# SCH_Line_Following_Robot_Interrupt_2023-.net
KiCad netlist of a schematic drawn in EasyEDA
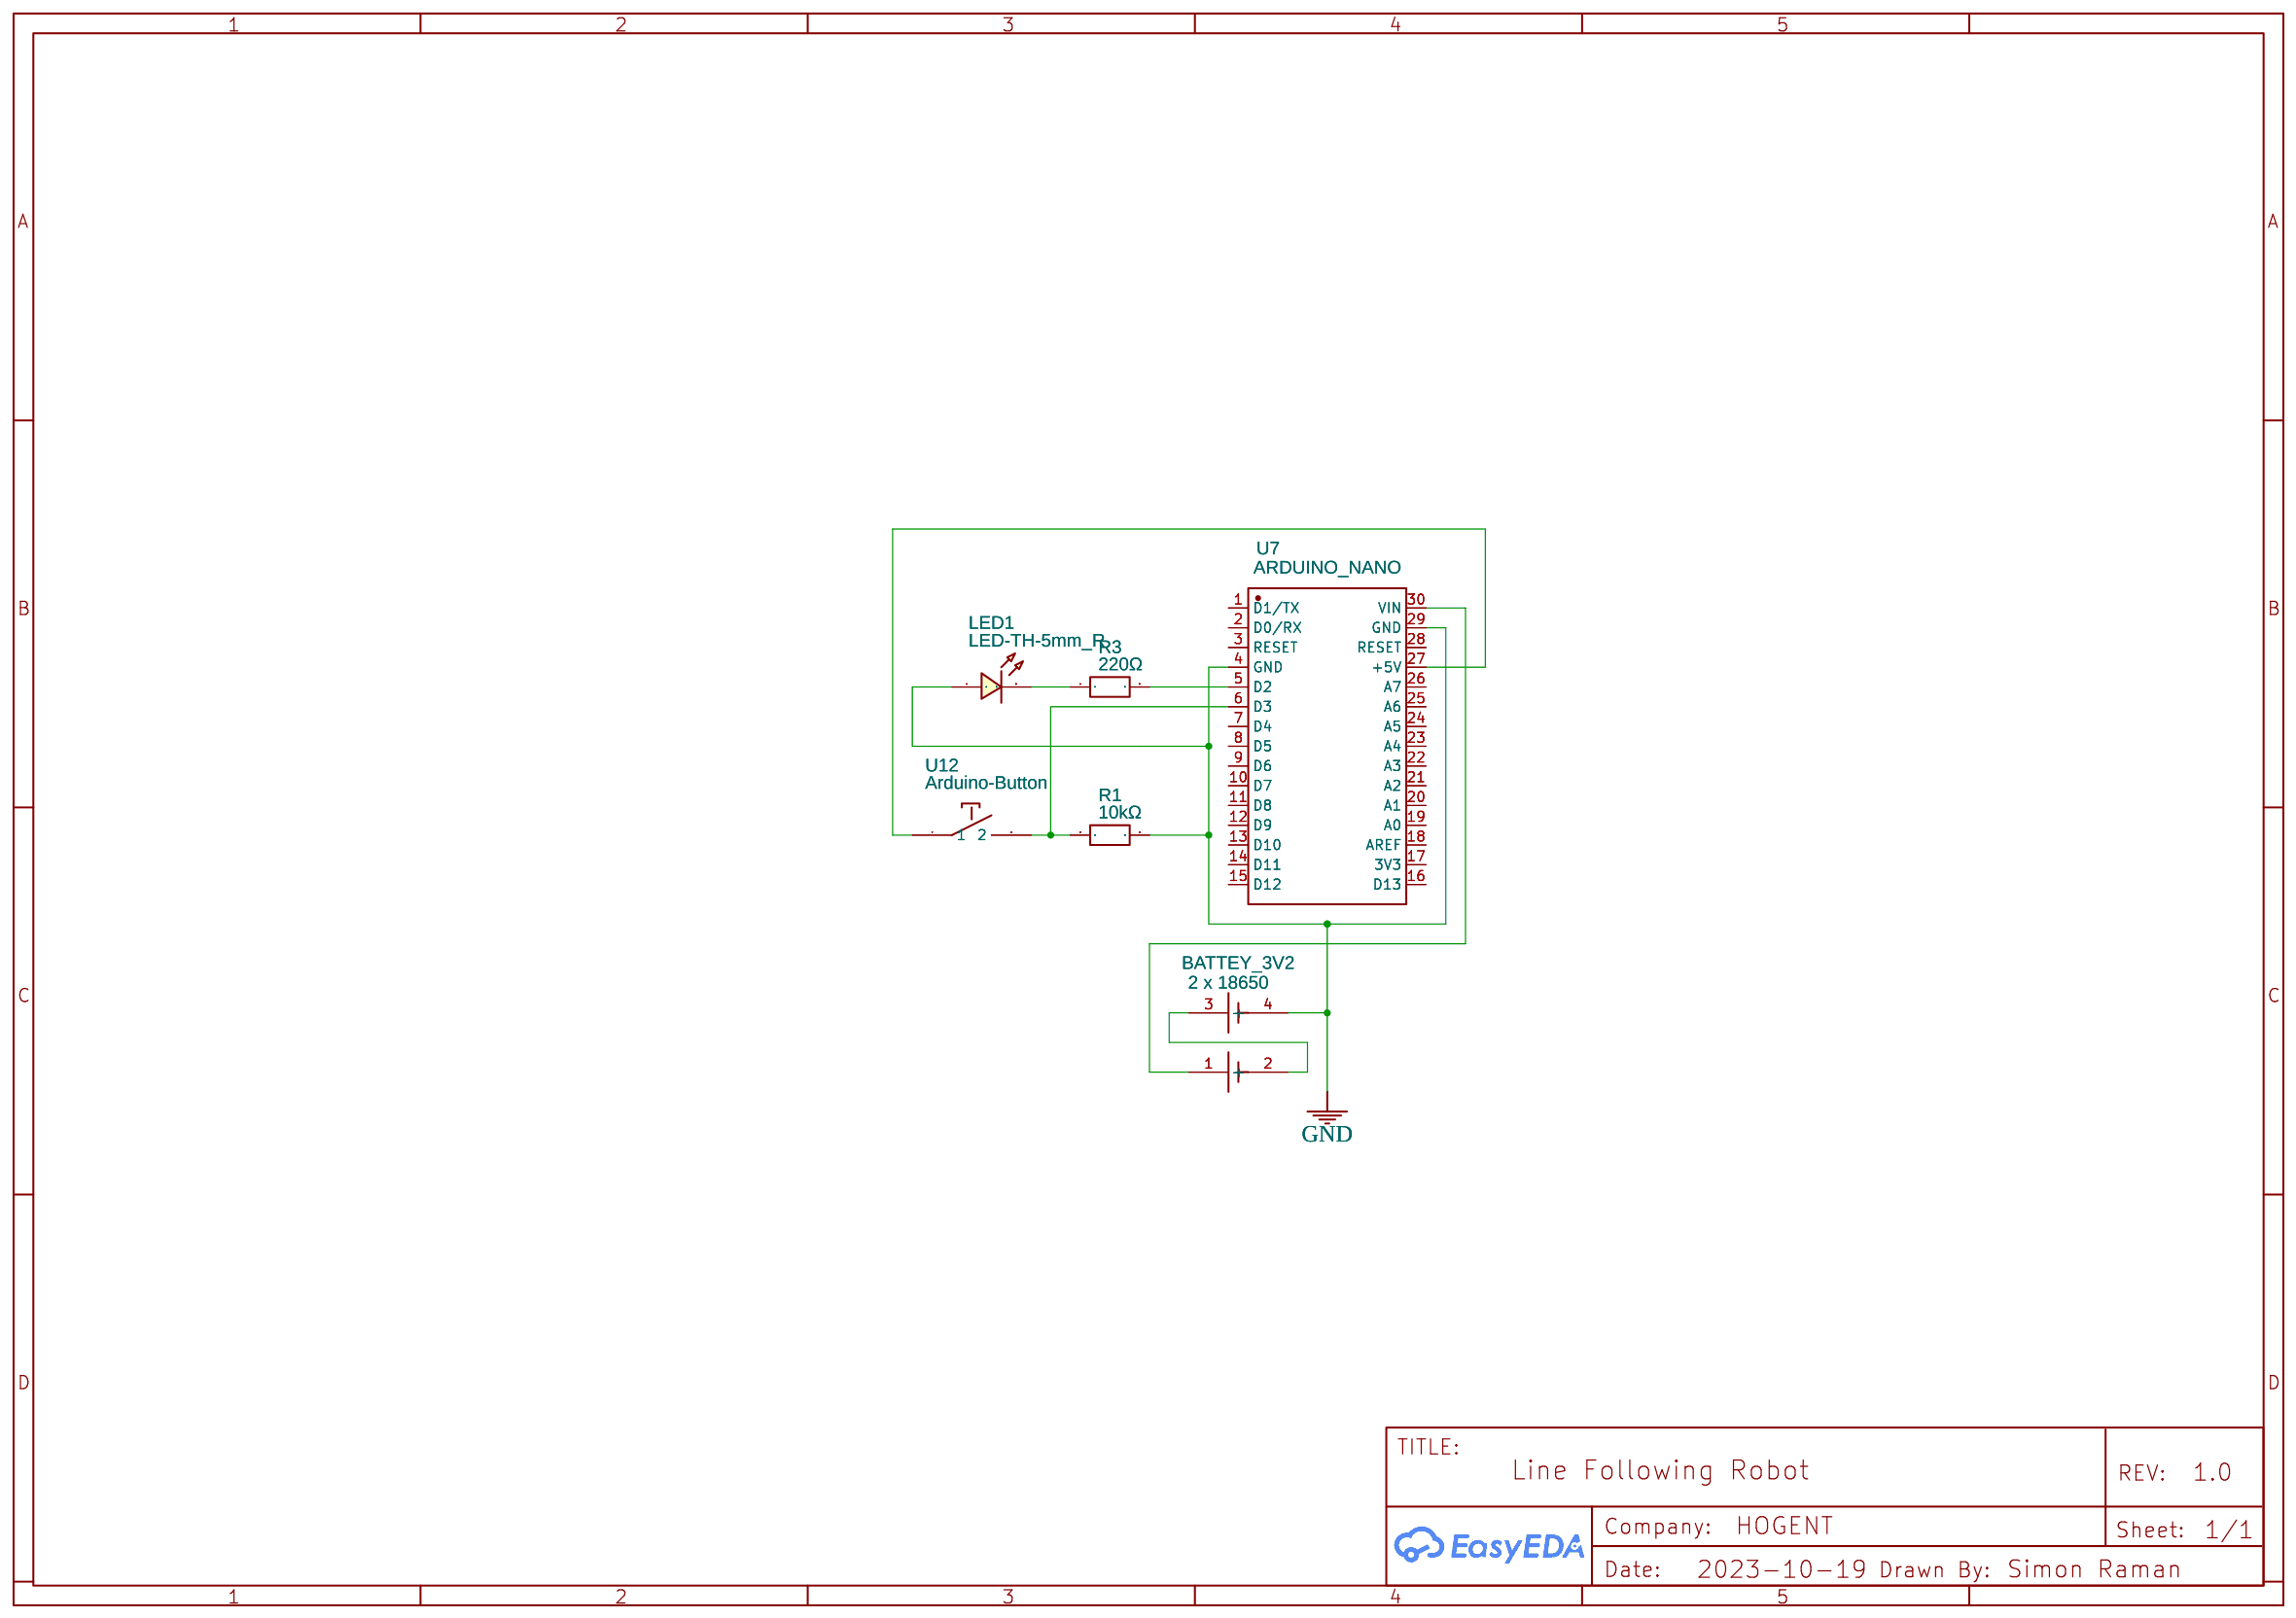
[diagram p0: schematic sheet]

(export (version "E")
  (design (tool "Eeschema 10.0.6"))
  (components
    (comp (ref "BATTEY_3V2")
      (value "2 x 18650")
      (fields (field (name "Manufacturer Part") "BAT_X2_18650") (field (name "Manufacturer") "Dex"))
      (libsource (lib "") (part "BAT_X2_18650"))
    )
    (comp (ref "LED1")
      (value "LED-TH-5mm_R")
      (fields
        (field (name "Manufacturer Part") "333-2SURD/S530-A3")
        (field (name "Manufacturer") "EVERLIGHT(台湾亿光)")
      )
      (libsource (lib "") (part "LED-TH-5mm_R"))
    )
    (comp (ref "R1")
      (value "10kΩ")
      (libsource (lib "") (part "AXIAL RESISTOR 220 OHM - TH_BD2.3-L6.0-P10.00-D0.4"))
    )
    (comp (ref "R3")
      (value "220Ω")
      (libsource (lib "") (part "AXIAL RESISTOR 220 OHM - TH_BD2.3-L6.0-P10.00-D0.4"))
    )
    (comp (ref "U7") (value "ARDUINO_NANO") (libsource (lib "") (part "ARDUINO_NANO")))
    (comp (ref "U12")
      (value "Arduino-Button")
      (fields (field (name "Manufacturer Part") "SW100664"))
      (libsource (lib "") (part "Arduino-Button"))
    )
  )
  (nets
    (net (code "1") (name "GND") (class "Default")
      (node (ref "BATTEY_3V2") (pin "4") (pinfunction "-_4") (pintype "unspecified"))
      (node (ref "LED1") (pin "1") (pinfunction "1_1") (pintype "unspecified"))
      (node (ref "R1") (pin "2") (pinfunction "2_2") (pintype "unspecified"))
      (node (ref "U7") (pin "29") (pinfunction "GND_29") (pintype "unspecified"))
      (node (ref "U7") (pin "4") (pinfunction "GND_4") (pintype "unspecified"))
    )
    (net (code "2") (name "Net-(BATTEY_3V2-+-Pad3)") (class "Default")
      (node (ref "BATTEY_3V2") (pin "2") (pinfunction "-_2") (pintype "unspecified"))
      (node (ref "BATTEY_3V2") (pin "3") (pinfunction "+_3") (pintype "unspecified"))
    )
    (net (code "3") (name "Net-(LED1-Pad2)") (class "Default")
      (node (ref "LED1") (pin "2") (pinfunction "2_2") (pintype "unspecified"))
      (node (ref "R3") (pin "1") (pinfunction "1_1") (pintype "unspecified"))
    )
    (net (code "4") (name "Net-(U7-+5V)") (class "Default")
      (node (ref "U12") (pin "1") (pinfunction "1_1") (pintype "unspecified"))
      (node (ref "U7") (pin "27") (pinfunction "+5V_27") (pintype "unspecified"))
    )
    (net (code "5") (name "Net-(U7-D2)") (class "Default")
      (node (ref "R3") (pin "2") (pinfunction "2_2") (pintype "unspecified"))
      (node (ref "U7") (pin "5") (pinfunction "D2_5") (pintype "unspecified"))
    )
    (net (code "6") (name "Net-(U7-D3)") (class "Default")
      (node (ref "R1") (pin "1") (pinfunction "1_1") (pintype "unspecified"))
      (node (ref "U12") (pin "2") (pinfunction "2_2") (pintype "unspecified"))
      (node (ref "U7") (pin "6") (pinfunction "D3_6") (pintype "unspecified"))
    )
    (net (code "7") (name "Net-(U7-VIN)") (class "Default")
      (node (ref "BATTEY_3V2") (pin "1") (pinfunction "+_1") (pintype "unspecified"))
      (node (ref "U7") (pin "30") (pinfunction "VIN_30") (pintype "unspecified"))
    )
    (net (code "8") (name "unconnected-(U7-3V3-Pad17)") (class "Default")
      (node (ref "U7") (pin "17") (pinfunction "3V3_17") (pintype "unspecified"))
    )
    (net (code "9") (name "unconnected-(U7-A0-Pad19)") (class "Default")
      (node (ref "U7") (pin "19") (pinfunction "A0_19") (pintype "unspecified"))
    )
    (net (code "10") (name "unconnected-(U7-A1-Pad20)") (class "Default")
      (node (ref "U7") (pin "20") (pinfunction "A1_20") (pintype "unspecified"))
    )
    (net (code "11") (name "unconnected-(U7-A2-Pad21)") (class "Default")
      (node (ref "U7") (pin "21") (pinfunction "A2_21") (pintype "unspecified"))
    )
    (net (code "12") (name "unconnected-(U7-A3-Pad22)") (class "Default")
      (node (ref "U7") (pin "22") (pinfunction "A3_22") (pintype "unspecified"))
    )
    (net (code "13") (name "unconnected-(U7-A4-Pad23)") (class "Default")
      (node (ref "U7") (pin "23") (pinfunction "A4_23") (pintype "unspecified"))
    )
    (net (code "14") (name "unconnected-(U7-A5-Pad24)") (class "Default")
      (node (ref "U7") (pin "24") (pinfunction "A5_24") (pintype "unspecified"))
    )
    (net (code "15") (name "unconnected-(U7-A6-Pad25)") (class "Default")
      (node (ref "U7") (pin "25") (pinfunction "A6_25") (pintype "unspecified"))
    )
    (net (code "16") (name "unconnected-(U7-A7-Pad26)") (class "Default")
      (node (ref "U7") (pin "26") (pinfunction "A7_26") (pintype "unspecified"))
    )
    (net (code "17") (name "unconnected-(U7-AREF-Pad18)") (class "Default")
      (node (ref "U7") (pin "18") (pinfunction "AREF_18") (pintype "unspecified"))
    )
    (net (code "18") (name "unconnected-(U7-D0{slash}RX-Pad2)") (class "Default")
      (node (ref "U7") (pin "2") (pinfunction "D0/RX_2") (pintype "unspecified"))
    )
    (net (code "19") (name "unconnected-(U7-D1{slash}TX-Pad1)") (class "Default")
      (node (ref "U7") (pin "1") (pinfunction "D1/TX_1") (pintype "unspecified"))
    )
    (net (code "20") (name "unconnected-(U7-D4-Pad7)") (class "Default")
      (node (ref "U7") (pin "7") (pinfunction "D4_7") (pintype "unspecified"))
    )
    (net (code "21") (name "unconnected-(U7-D5-Pad8)") (class "Default")
      (node (ref "U7") (pin "8") (pinfunction "D5_8") (pintype "unspecified"))
    )
    (net (code "22") (name "unconnected-(U7-D6-Pad9)") (class "Default")
      (node (ref "U7") (pin "9") (pinfunction "D6_9") (pintype "unspecified"))
    )
    (net (code "23") (name "unconnected-(U7-D7-Pad10)") (class "Default")
      (node (ref "U7") (pin "10") (pinfunction "D7_10") (pintype "unspecified"))
    )
    (net (code "24") (name "unconnected-(U7-D8-Pad11)") (class "Default")
      (node (ref "U7") (pin "11") (pinfunction "D8_11") (pintype "unspecified"))
    )
    (net (code "25") (name "unconnected-(U7-D9-Pad12)") (class "Default")
      (node (ref "U7") (pin "12") (pinfunction "D9_12") (pintype "unspecified"))
    )
    (net (code "26") (name "unconnected-(U7-D10-Pad13)") (class "Default")
      (node (ref "U7") (pin "13") (pinfunction "D10_13") (pintype "unspecified"))
    )
    (net (code "27") (name "unconnected-(U7-D11-Pad14)") (class "Default")
      (node (ref "U7") (pin "14") (pinfunction "D11_14") (pintype "unspecified"))
    )
    (net (code "28") (name "unconnected-(U7-D12-Pad15)") (class "Default")
      (node (ref "U7") (pin "15") (pinfunction "D12_15") (pintype "unspecified"))
    )
    (net (code "29") (name "unconnected-(U7-D13-Pad16)") (class "Default")
      (node (ref "U7") (pin "16") (pinfunction "D13_16") (pintype "unspecified"))
    )
    (net (code "30") (name "unconnected-(U7-RESET-Pad3)") (class "Default")
      (node (ref "U7") (pin "3") (pinfunction "RESET_3") (pintype "unspecified"))
    )
    (net (code "31") (name "unconnected-(U7-RESET-Pad28)") (class "Default")
      (node (ref "U7") (pin "28") (pinfunction "RESET_28") (pintype "unspecified"))
    )
  )
)
